# Sheet1.net
KiCad netlist of a schematic drawn in Altium Designer
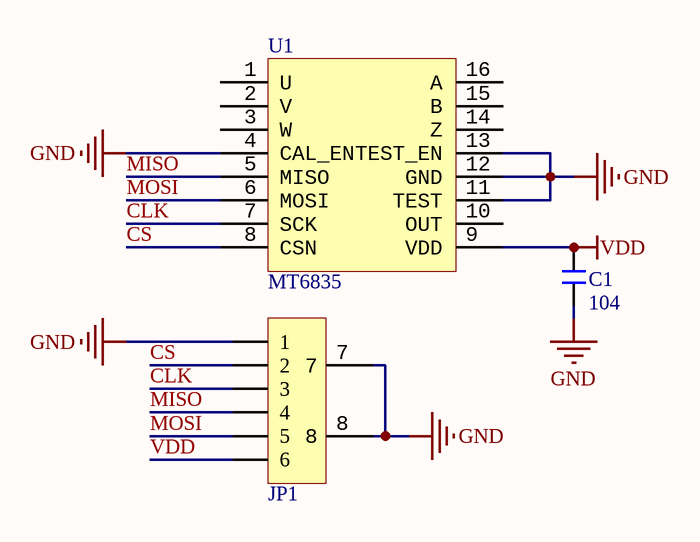
[diagram p0: Sheet1.SchDoc]

(export (version "E")
  (design (tool "Eeschema 10.0.6"))
  (components
    (comp (ref "C1")
      (value "104")
      (footprint "C 0402_L")
      (description "无极性贴片电容")
      (fields (field (name "版权归属") "源创客"))
      (libsource (lib "3.1   - 电阻-电容-电感") (part "C"))
    )
    (comp (ref "JP1")
      (value "HDR-1X6")
      (footprint "GH1.25-WS-6P")
      (description "6P接插件")
      (fields (field (name "版权归属") "源创客"))
      (libsource (lib "4.2   - 接插件-脚距1.25") (part "Header 6"))
    )
    (comp (ref "U1")
      (value "MT6835")
      (footprint "TSSOP16_L")
      (description "21bit磁编码芯片")
      (libsource (lib "1.1   - IC芯片") (part "MT6835"))
    )
  )
  (nets
    (net (code "1") (name "/CLK") (class "Default")
      (node (ref "JP1") (pin "3") (pinfunction "3_3") (pintype "passive"))
      (node (ref "U1") (pin "7") (pinfunction "SCK_7") (pintype "passive"))
    )
    (net (code "2") (name "/CS") (class "Default")
      (node (ref "JP1") (pin "2") (pinfunction "2_2") (pintype "passive"))
      (node (ref "U1") (pin "8") (pinfunction "CSN_8") (pintype "passive"))
    )
    (net (code "3") (name "/MISO") (class "Default")
      (node (ref "JP1") (pin "4") (pinfunction "4_4") (pintype "passive"))
      (node (ref "U1") (pin "5") (pinfunction "MISO_5") (pintype "passive"))
    )
    (net (code "4") (name "/MOSI") (class "Default")
      (node (ref "JP1") (pin "5") (pinfunction "5_5") (pintype "passive"))
      (node (ref "U1") (pin "6") (pinfunction "MOSI_6") (pintype "passive"))
    )
    (net (code "5") (name "GND") (class "Default")
      (node (ref "C1") (pin "1") (pinfunction "1_1") (pintype "passive"))
      (node (ref "JP1") (pin "1") (pinfunction "1_1") (pintype "passive"))
      (node (ref "JP1") (pin "7") (pinfunction "7_7") (pintype "passive"))
      (node (ref "JP1") (pin "8") (pinfunction "8_8") (pintype "passive"))
      (node (ref "U1") (pin "11") (pinfunction "TEST_11") (pintype "passive"))
      (node (ref "U1") (pin "12") (pinfunction "GND_12") (pintype "passive"))
      (node (ref "U1") (pin "13") (pinfunction "TEST_EN_13") (pintype "passive"))
      (node (ref "U1") (pin "4") (pinfunction "CAL_EN_4") (pintype "passive"))
    )
    (net (code "6") (name "VDD") (class "Default")
      (node (ref "C1") (pin "2") (pinfunction "2_2") (pintype "passive"))
      (node (ref "JP1") (pin "6") (pinfunction "6_6") (pintype "passive"))
      (node (ref "U1") (pin "9") (pinfunction "VDD_9") (pintype "passive"))
    )
    (net (code "7") (name "unconnected-(U1-A-Pad16)") (class "Default")
      (node (ref "U1") (pin "16") (pinfunction "A_16") (pintype "passive"))
    )
    (net (code "8") (name "unconnected-(U1-B-Pad15)") (class "Default")
      (node (ref "U1") (pin "15") (pinfunction "B_15") (pintype "passive"))
    )
    (net (code "9") (name "unconnected-(U1-OUT-Pad10)") (class "Default")
      (node (ref "U1") (pin "10") (pinfunction "OUT_10") (pintype "passive"))
    )
    (net (code "10") (name "unconnected-(U1-U-Pad1)") (class "Default")
      (node (ref "U1") (pin "1") (pinfunction "U_1") (pintype "passive"))
    )
    (net (code "11") (name "unconnected-(U1-V-Pad2)") (class "Default")
      (node (ref "U1") (pin "2") (pinfunction "V_2") (pintype "passive"))
    )
    (net (code "12") (name "unconnected-(U1-W-Pad3)") (class "Default")
      (node (ref "U1") (pin "3") (pinfunction "W_3") (pintype "passive"))
    )
    (net (code "13") (name "unconnected-(U1-Z-Pad14)") (class "Default")
      (node (ref "U1") (pin "14") (pinfunction "Z_14") (pintype "passive"))
    )
  )
)
